# Hbridge.net
KiCad netlist of a schematic drawn in Altium Designer
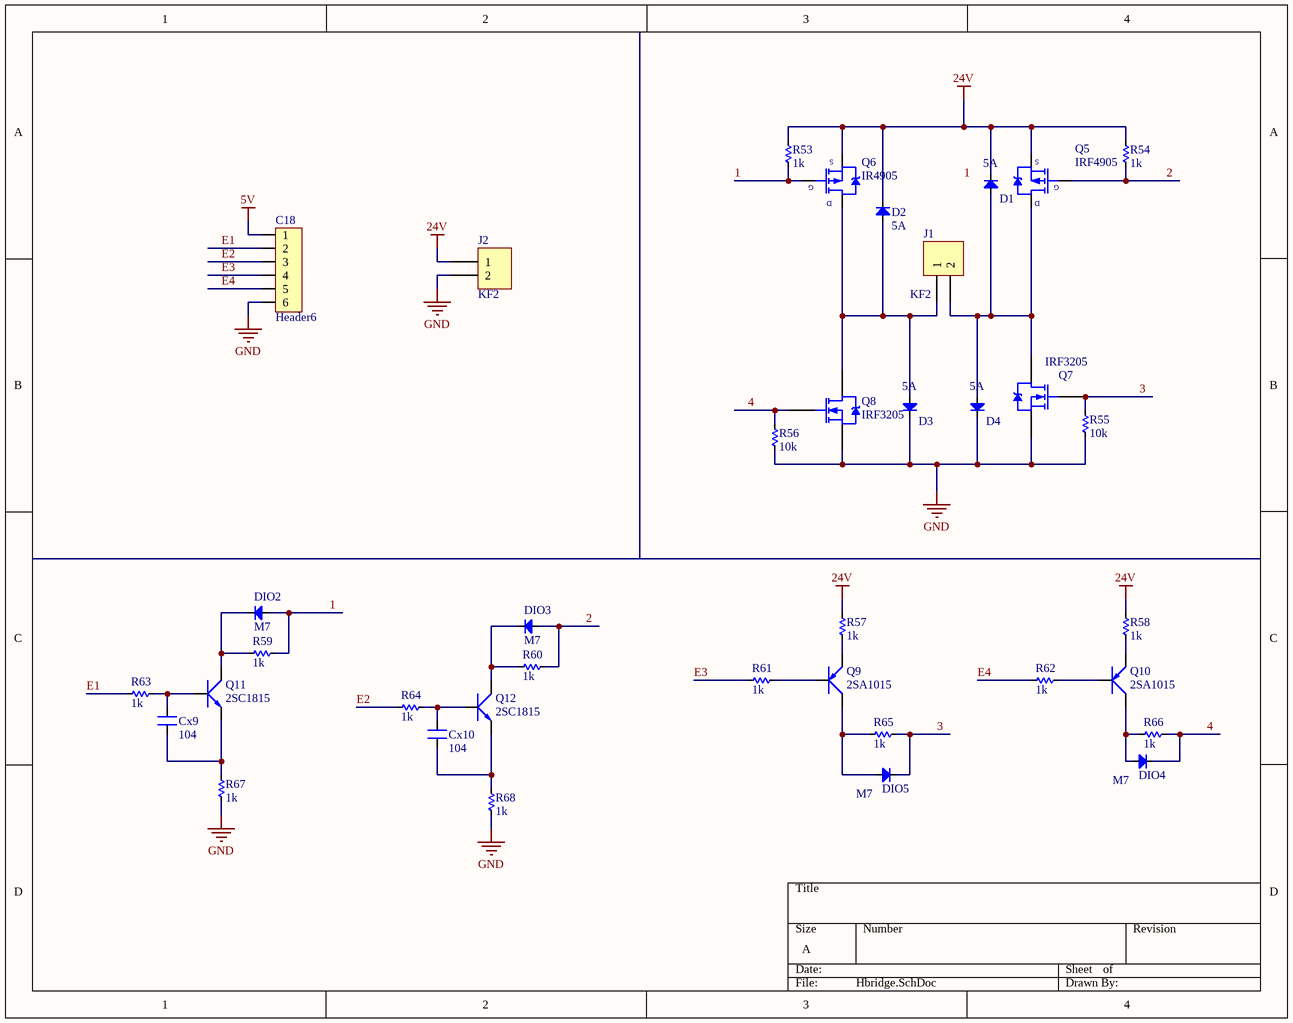
[diagram p0: Hbridge.SchDoc]

(export (version "E")
  (design (tool "Eeschema 10.0.6"))
  (components
    (comp (ref "C18")
      (value "Header6")
      (footprint "HDR6")
      (description "Header IDC, 6 x 1 Pin Vertical 2.54mm Pitch (Non-Boxed, Male)")
      (fields
        (field (name "MANUFACTURER") "Würth Elektronik eiSos GmbH")
        (field (name "PARTNO") "613002143121")
        (field (name "CREATED BY") "Karrer Zheng")
      )
      (libsource (lib "LIBRARY") (part "Header6"))
    )
    (comp (ref "Cx9") (value "104") (footprint "CN-SMD-0805") (libsource (lib "LIBRARY") (part "CN")))
    (comp (ref "Cx10") (value "104") (footprint "CN-SMD-0805") (libsource (lib "LIBRARY") (part "CN")))
    (comp (ref "D1")
      (value "5A")
      (footprint "DIO-5A")
      (description "Default Diode TMS")
      (fields (field (name "PUBLISHER") "Altium Limited"))
      (libsource (lib "LIBRARY") (part "Diode"))
    )
    (comp (ref "D2")
      (value "5A")
      (footprint "DIO-5A")
      (description "Default Diode TMS")
      (fields (field (name "PUBLISHER") "Altium Limited"))
      (libsource (lib "LIBRARY") (part "Diode"))
    )
    (comp (ref "D3")
      (value "5A")
      (footprint "DIO-5A")
      (description "Default Diode TMS")
      (fields (field (name "PUBLISHER") "Altium Limited"))
      (libsource (lib "LIBRARY") (part "Diode"))
    )
    (comp (ref "D4")
      (value "5A")
      (footprint "DIO-5A")
      (description "Default Diode TMS")
      (fields (field (name "PUBLISHER") "Altium Limited"))
      (libsource (lib "LIBRARY") (part "Diode"))
    )
    (comp (ref "DIO2")
      (value "M7")
      (footprint "DIO-SMD-106")
      (description "Default Diode")
      (fields (field (name "PUBLISHER") "Altium Limited"))
      (libsource (lib "LIBRARY") (part "Diode SMD"))
    )
    (comp (ref "DIO3")
      (value "M7")
      (footprint "DIO-SMD-106")
      (description "Default Diode")
      (fields (field (name "PUBLISHER") "Altium Limited"))
      (libsource (lib "LIBRARY") (part "Diode SMD"))
    )
    (comp (ref "DIO4")
      (value "M7")
      (footprint "DIO-SMD-106")
      (description "Default Diode")
      (fields (field (name "PUBLISHER") "Altium Limited"))
      (libsource (lib "LIBRARY") (part "Diode SMD"))
    )
    (comp (ref "DIO5")
      (value "M7")
      (footprint "DIO-SMD-106")
      (description "Default Diode")
      (fields (field (name "PUBLISHER") "Altium Limited"))
      (libsource (lib "LIBRARY") (part "Diode SMD"))
    )
    (comp (ref "J1")
      (value "KF2")
      (footprint "KF2-7.62")
      (fields
        (field (name "MANUFACTURER") "Würth Elektronik eiSos GmbH")
        (field (name "PARTNO") "691103110002")
        (field (name "CREATED BY") "Karrer Zheng")
      )
      (libsource (lib "") (part "KF2_1"))
    )
    (comp (ref "J2")
      (value "KF2")
      (footprint "KF2-7.62")
      (fields
        (field (name "MANUFACTURER") "Würth Elektronik eiSos GmbH")
        (field (name "PARTNO") "691103110002")
        (field (name "CREATED BY") "Karrer Zheng")
      )
      (libsource (lib "LIBRARY") (part "KF2"))
    )
    (comp (ref "Q5")
      (value "IRF4905")
      (footprint "TO220-123")
      (description "HEXFET P-Channel Power MOSFET")
      (libsource (lib "LIBRARY") (part "IRF9540"))
    )
    (comp (ref "Q6")
      (value "IR4905")
      (footprint "TO220-123")
      (description "HEXFET P-Channel Power MOSFET")
      (libsource (lib "LIBRARY") (part "IRF9540"))
    )
    (comp (ref "Q7") (value "IRF3205") (footprint "TO220-123") (libsource (lib "LIBRARY") (part "IRFZ44")))
    (comp (ref "Q8") (value "IRF3205") (footprint "TO220-123") (libsource (lib "LIBRARY") (part "IRFZ44")))
    (comp (ref "Q9")
      (value "2SA1015")
      (footprint "SOT23-321")
      (description "PNP 600mW, ECB")
      (libsource (lib "LIBRARY") (part "2SA1015"))
    )
    (comp (ref "Q10")
      (value "2SA1015")
      (footprint "SOT23-321")
      (description "PNP 600mW, ECB")
      (libsource (lib "LIBRARY") (part "2SA1015"))
    )
    (comp (ref "Q11")
      (value "2SC1815")
      (footprint "SOT23-321")
      (description "NPN 600mW, ECB")
      (libsource (lib "LIBRARY") (part "2SC1815"))
    )
    (comp (ref "Q12")
      (value "2SC1815")
      (footprint "SOT23-321")
      (description "NPN 600mW, ECB")
      (libsource (lib "LIBRARY") (part "2SC1815"))
    )
    (comp (ref "R53")
      (value "1k")
      (footprint "RES-1/4W-SMALL")
      (description "Res")
      (fields
        (field (name "MANUFACTURER") "Generic Components")
        (field (name "PUBLISHER") "Altium Hobart Technology Centre")
      )
      (libsource (lib "LIBRARY") (part "Res"))
    )
    (comp (ref "R54")
      (value "1k")
      (footprint "RES-1/4W-SMALL")
      (description "Res")
      (fields
        (field (name "MANUFACTURER") "Generic Components")
        (field (name "PUBLISHER") "Altium Hobart Technology Centre")
      )
      (libsource (lib "LIBRARY") (part "Res"))
    )
    (comp (ref "R55")
      (value "10k")
      (footprint "RES-1/4W-SMALL")
      (description "Res")
      (fields
        (field (name "MANUFACTURER") "Generic Components")
        (field (name "PUBLISHER") "Altium Hobart Technology Centre")
      )
      (libsource (lib "LIBRARY") (part "Res"))
    )
    (comp (ref "R56")
      (value "10k")
      (footprint "RES-1/4W-SMALL")
      (description "Res")
      (fields
        (field (name "MANUFACTURER") "Generic Components")
        (field (name "PUBLISHER") "Altium Hobart Technology Centre")
      )
      (libsource (lib "LIBRARY") (part "Res"))
    )
    (comp (ref "R57")
      (value "1k")
      (footprint "RES-SMD-0805")
      (description "Resistor")
      (fields
        (field (name "MANUFACTURER") "Generic Components")
        (field (name "PUBLISHER") "Altium Hobart Technology Centre")
      )
      (libsource (lib "LIBRARY") (part "Res-SMD"))
    )
    (comp (ref "R58")
      (value "1k")
      (footprint "RES-SMD-0805")
      (description "Resistor")
      (fields
        (field (name "MANUFACTURER") "Generic Components")
        (field (name "PUBLISHER") "Altium Hobart Technology Centre")
      )
      (libsource (lib "LIBRARY") (part "Res-SMD"))
    )
    (comp (ref "R59")
      (value "1k")
      (footprint "RES-SMD-0805")
      (description "Resistor")
      (fields
        (field (name "MANUFACTURER") "Generic Components")
        (field (name "PUBLISHER") "Altium Hobart Technology Centre")
      )
      (libsource (lib "LIBRARY") (part "Res-SMD"))
    )
    (comp (ref "R60")
      (value "1k")
      (footprint "RES-SMD-0805")
      (description "Resistor")
      (fields
        (field (name "MANUFACTURER") "Generic Components")
        (field (name "PUBLISHER") "Altium Hobart Technology Centre")
      )
      (libsource (lib "LIBRARY") (part "Res-SMD"))
    )
    (comp (ref "R61")
      (value "1k")
      (footprint "RES-SMD-0805")
      (description "Resistor")
      (fields
        (field (name "MANUFACTURER") "Generic Components")
        (field (name "PUBLISHER") "Altium Hobart Technology Centre")
      )
      (libsource (lib "LIBRARY") (part "Res-SMD"))
    )
    (comp (ref "R62")
      (value "1k")
      (footprint "RES-SMD-0805")
      (description "Resistor")
      (fields
        (field (name "MANUFACTURER") "Generic Components")
        (field (name "PUBLISHER") "Altium Hobart Technology Centre")
      )
      (libsource (lib "LIBRARY") (part "Res-SMD"))
    )
    (comp (ref "R63")
      (value "1k")
      (footprint "RES-SMD-0805")
      (description "Resistor")
      (fields
        (field (name "MANUFACTURER") "Generic Components")
        (field (name "PUBLISHER") "Altium Hobart Technology Centre")
      )
      (libsource (lib "LIBRARY") (part "Res-SMD"))
    )
    (comp (ref "R64")
      (value "1k")
      (footprint "RES-SMD-0805")
      (description "Resistor")
      (fields
        (field (name "MANUFACTURER") "Generic Components")
        (field (name "PUBLISHER") "Altium Hobart Technology Centre")
      )
      (libsource (lib "LIBRARY") (part "Res-SMD"))
    )
    (comp (ref "R65")
      (value "1k")
      (footprint "RES-SMD-0805")
      (description "Resistor")
      (fields
        (field (name "MANUFACTURER") "Generic Components")
        (field (name "PUBLISHER") "Altium Hobart Technology Centre")
      )
      (libsource (lib "LIBRARY") (part "Res-SMD"))
    )
    (comp (ref "R66")
      (value "1k")
      (footprint "RES-SMD-0805")
      (description "Resistor")
      (fields
        (field (name "MANUFACTURER") "Generic Components")
        (field (name "PUBLISHER") "Altium Hobart Technology Centre")
      )
      (libsource (lib "LIBRARY") (part "Res-SMD"))
    )
    (comp (ref "R67")
      (value "1k")
      (footprint "RES-SMD-0805")
      (description "Resistor")
      (fields
        (field (name "MANUFACTURER") "Generic Components")
        (field (name "PUBLISHER") "Altium Hobart Technology Centre")
      )
      (libsource (lib "LIBRARY") (part "Res-SMD"))
    )
    (comp (ref "R68")
      (value "1k")
      (footprint "RES-SMD-0805")
      (description "Resistor")
      (fields
        (field (name "MANUFACTURER") "Generic Components")
        (field (name "PUBLISHER") "Altium Hobart Technology Centre")
      )
      (libsource (lib "LIBRARY") (part "Res-SMD"))
    )
  )
  (nets
    (net (code "1") (name "/1") (class "Default")
      (node (ref "DIO2") (pin "1") (pinfunction "A_1") (pintype "passive"))
      (node (ref "Q6") (pin "1") (pinfunction "G_1") (pintype "passive"))
      (node (ref "R53") (pin "2") (pinfunction "2_2") (pintype "passive"))
      (node (ref "R59") (pin "1") (pinfunction "1_1") (pintype "passive"))
    )
    (net (code "2") (name "/2") (class "Default")
      (node (ref "DIO3") (pin "1") (pinfunction "A_1") (pintype "passive"))
      (node (ref "Q5") (pin "1") (pinfunction "G_1") (pintype "passive"))
      (node (ref "R54") (pin "2") (pinfunction "2_2") (pintype "passive"))
      (node (ref "R60") (pin "1") (pinfunction "1_1") (pintype "passive"))
    )
    (net (code "3") (name "/3") (class "Default")
      (node (ref "DIO5") (pin "2") (pinfunction "K_2") (pintype "passive"))
      (node (ref "Q7") (pin "1") (pinfunction "G_1") (pintype "passive"))
      (node (ref "R55") (pin "1") (pinfunction "1_1") (pintype "passive"))
      (node (ref "R65") (pin "1") (pinfunction "1_1") (pintype "passive"))
    )
    (net (code "4") (name "/4") (class "Default")
      (node (ref "DIO4") (pin "2") (pinfunction "K_2") (pintype "passive"))
      (node (ref "Q8") (pin "1") (pinfunction "G_1") (pintype "passive"))
      (node (ref "R56") (pin "1") (pinfunction "1_1") (pintype "passive"))
      (node (ref "R66") (pin "1") (pinfunction "1_1") (pintype "passive"))
    )
    (net (code "5") (name "/E1") (class "Default")
      (node (ref "C18") (pin "2") (pinfunction "2_2") (pintype "passive"))
      (node (ref "R63") (pin "2") (pinfunction "2_2") (pintype "passive"))
    )
    (net (code "6") (name "/E2") (class "Default")
      (node (ref "C18") (pin "3") (pinfunction "3_3") (pintype "passive"))
      (node (ref "R64") (pin "2") (pinfunction "2_2") (pintype "passive"))
    )
    (net (code "7") (name "/E3") (class "Default")
      (node (ref "C18") (pin "4") (pinfunction "4_4") (pintype "passive"))
      (node (ref "R61") (pin "2") (pinfunction "2_2") (pintype "passive"))
    )
    (net (code "8") (name "/E4") (class "Default")
      (node (ref "C18") (pin "5") (pinfunction "5_5") (pintype "passive"))
      (node (ref "R62") (pin "2") (pinfunction "2_2") (pintype "passive"))
    )
    (net (code "9") (name "5V") (class "Default")
      (node (ref "C18") (pin "1") (pinfunction "1_1") (pintype "passive"))
    )
    (net (code "10") (name "24V") (class "Default")
      (node (ref "D1") (pin "2") (pinfunction "K_2") (pintype "passive"))
      (node (ref "D2") (pin "2") (pinfunction "K_2") (pintype "passive"))
      (node (ref "J2") (pin "1") (pinfunction "1_1") (pintype "passive"))
      (node (ref "Q5") (pin "3") (pinfunction "S_3") (pintype "passive"))
      (node (ref "Q6") (pin "3") (pinfunction "S_3") (pintype "passive"))
      (node (ref "R53") (pin "1") (pinfunction "1_1") (pintype "passive"))
      (node (ref "R54") (pin "1") (pinfunction "1_1") (pintype "passive"))
      (node (ref "R57") (pin "1") (pinfunction "1_1") (pintype "passive"))
      (node (ref "R58") (pin "1") (pinfunction "1_1") (pintype "passive"))
    )
    (net (code "11") (name "GND") (class "Default")
      (node (ref "C18") (pin "6") (pinfunction "6_6") (pintype "passive"))
      (node (ref "D3") (pin "2") (pinfunction "K_2") (pintype "passive"))
      (node (ref "D4") (pin "2") (pinfunction "K_2") (pintype "passive"))
      (node (ref "J2") (pin "2") (pinfunction "2_2") (pintype "passive"))
      (node (ref "Q7") (pin "3") (pinfunction "S_3") (pintype "passive"))
      (node (ref "Q8") (pin "3") (pinfunction "S_3") (pintype "passive"))
      (node (ref "R55") (pin "2") (pinfunction "2_2") (pintype "passive"))
      (node (ref "R56") (pin "2") (pinfunction "2_2") (pintype "passive"))
      (node (ref "R67") (pin "2") (pinfunction "2_2") (pintype "passive"))
      (node (ref "R68") (pin "2") (pinfunction "2_2") (pintype "passive"))
    )
    (net (code "12") (name "Net-(D1-A)") (class "Default")
      (node (ref "D1") (pin "1") (pinfunction "A_1") (pintype "passive"))
      (node (ref "D4") (pin "1") (pinfunction "A_1") (pintype "passive"))
      (node (ref "J1") (pin "2") (pinfunction "2_2") (pintype "passive"))
      (node (ref "Q5") (pin "2") (pinfunction "D_2") (pintype "passive"))
      (node (ref "Q7") (pin "2") (pinfunction "D_2") (pintype "passive"))
    )
    (net (code "13") (name "Net-(D2-A)") (class "Default")
      (node (ref "D2") (pin "1") (pinfunction "A_1") (pintype "passive"))
      (node (ref "D3") (pin "1") (pinfunction "A_1") (pintype "passive"))
      (node (ref "J1") (pin "1") (pinfunction "1_1") (pintype "passive"))
      (node (ref "Q6") (pin "2") (pinfunction "D_2") (pintype "passive"))
      (node (ref "Q8") (pin "2") (pinfunction "D_2") (pintype "passive"))
    )
    (net (code "14") (name "Net-(DIO2-K)") (class "Default")
      (node (ref "DIO2") (pin "2") (pinfunction "K_2") (pintype "passive"))
      (node (ref "Q11") (pin "2") (pinfunction "C_2") (pintype "passive"))
      (node (ref "R59") (pin "2") (pinfunction "2_2") (pintype "passive"))
    )
    (net (code "15") (name "Net-(DIO3-K)") (class "Default")
      (node (ref "DIO3") (pin "2") (pinfunction "K_2") (pintype "passive"))
      (node (ref "Q12") (pin "2") (pinfunction "C_2") (pintype "passive"))
      (node (ref "R60") (pin "2") (pinfunction "2_2") (pintype "passive"))
    )
    (net (code "16") (name "Net-(DIO4-A)") (class "Default")
      (node (ref "DIO4") (pin "1") (pinfunction "A_1") (pintype "passive"))
      (node (ref "Q10") (pin "2") (pinfunction "C_2") (pintype "passive"))
      (node (ref "R66") (pin "2") (pinfunction "2_2") (pintype "passive"))
    )
    (net (code "17") (name "Net-(DIO5-A)") (class "Default")
      (node (ref "DIO5") (pin "1") (pinfunction "A_1") (pintype "passive"))
      (node (ref "Q9") (pin "2") (pinfunction "C_2") (pintype "passive"))
      (node (ref "R65") (pin "2") (pinfunction "2_2") (pintype "passive"))
    )
    (net (code "18") (name "Net-(Q9-B)") (class "Default")
      (node (ref "Q9") (pin "3") (pinfunction "B_3") (pintype "passive"))
      (node (ref "R61") (pin "1") (pinfunction "1_1") (pintype "passive"))
    )
    (net (code "19") (name "Net-(Q9-E)") (class "Default")
      (node (ref "Q9") (pin "1") (pinfunction "E_1") (pintype "passive"))
      (node (ref "R57") (pin "2") (pinfunction "2_2") (pintype "passive"))
    )
    (net (code "20") (name "Net-(Q10-B)") (class "Default")
      (node (ref "Q10") (pin "3") (pinfunction "B_3") (pintype "passive"))
      (node (ref "R62") (pin "1") (pinfunction "1_1") (pintype "passive"))
    )
    (net (code "21") (name "Net-(Q10-E)") (class "Default")
      (node (ref "Q10") (pin "1") (pinfunction "E_1") (pintype "passive"))
      (node (ref "R58") (pin "2") (pinfunction "2_2") (pintype "passive"))
    )
    (net (code "22") (name "Net-(Q11-B)") (class "Default")
      (node (ref "Cx9") (pin "2") (pinfunction "2_2") (pintype "passive"))
      (node (ref "Q11") (pin "3") (pinfunction "B_3") (pintype "passive"))
      (node (ref "R63") (pin "1") (pinfunction "1_1") (pintype "passive"))
    )
    (net (code "23") (name "Net-(Q11-E)") (class "Default")
      (node (ref "Cx9") (pin "1") (pinfunction "1_1") (pintype "passive"))
      (node (ref "Q11") (pin "1") (pinfunction "E_1") (pintype "passive"))
      (node (ref "R67") (pin "1") (pinfunction "1_1") (pintype "passive"))
    )
    (net (code "24") (name "Net-(Q12-B)") (class "Default")
      (node (ref "Cx10") (pin "2") (pinfunction "2_2") (pintype "passive"))
      (node (ref "Q12") (pin "3") (pinfunction "B_3") (pintype "passive"))
      (node (ref "R64") (pin "1") (pinfunction "1_1") (pintype "passive"))
    )
    (net (code "25") (name "Net-(Q12-E)") (class "Default")
      (node (ref "Cx10") (pin "1") (pinfunction "1_1") (pintype "passive"))
      (node (ref "Q12") (pin "1") (pinfunction "E_1") (pintype "passive"))
      (node (ref "R68") (pin "1") (pinfunction "1_1") (pintype "passive"))
    )
  )
)
